# 09_IO_Isolated_Interface.net
KiCad netlist of a schematic drawn in Altium Designer
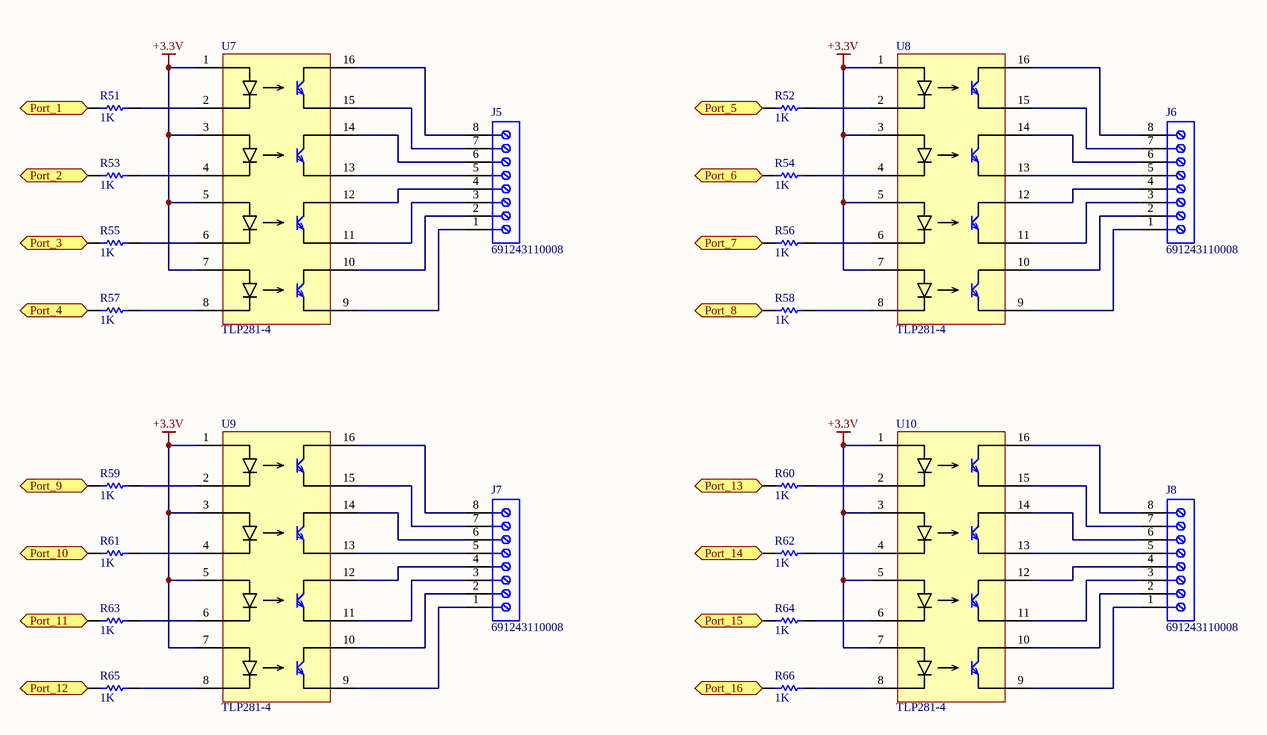
[diagram p0: 09_IO_Isolated_Interface.SchDoc]

(export (version "E")
  (design (tool "Eeschema 10.0.6"))
  (components
    (comp (ref "J5")
      (value "691243110008")
      (footprint "691243110008")
      (description "WR-TBL Serie 2431 Horizontal Cable Entry, Rising Cage Clamp, pitch 3.5mm, 8p")
      (fields (field (name "PUBLISHER") "Wurth Elektronik"))
      (libsource (lib "691322310002.") (part "691243110008"))
    )
    (comp (ref "J6")
      (value "691243110008")
      (footprint "691243110008")
      (description "WR-TBL Serie 2431 Horizontal Cable Entry, Rising Cage Clamp, pitch 3.5mm, 8p")
      (fields (field (name "PUBLISHER") "Wurth Elektronik"))
      (libsource (lib "691322310002.") (part "691243110008"))
    )
    (comp (ref "J7")
      (value "691243110008")
      (footprint "691243110008")
      (description "WR-TBL Serie 2431 Horizontal Cable Entry, Rising Cage Clamp, pitch 3.5mm, 8p")
      (fields (field (name "PUBLISHER") "Wurth Elektronik"))
      (libsource (lib "691322310002.") (part "691243110008"))
    )
    (comp (ref "J8")
      (value "691243110008")
      (footprint "691243110008")
      (description "WR-TBL Serie 2431 Horizontal Cable Entry, Rising Cage Clamp, pitch 3.5mm, 8p")
      (fields (field (name "PUBLISHER") "Wurth Elektronik"))
      (libsource (lib "691322310002.") (part "691243110008"))
    )
    (comp (ref "R51")
      (value "1K")
      (footprint "RES-SM-0603")
      (description "Resistor")
      (fields (field (name "Comment") "RESISTOR SMD"))
      (libsource (lib "PIF_Library") (part "RESISTOR SMD"))
    )
    (comp (ref "R52")
      (value "1K")
      (footprint "RES-SM-0603")
      (description "Resistor")
      (fields (field (name "Comment") "RESISTOR SMD"))
      (libsource (lib "PIF_Library") (part "RESISTOR SMD"))
    )
    (comp (ref "R53")
      (value "1K")
      (footprint "RES-SM-0603")
      (description "Resistor")
      (fields (field (name "Comment") "RESISTOR SMD"))
      (libsource (lib "PIF_Library") (part "RESISTOR SMD"))
    )
    (comp (ref "R54")
      (value "1K")
      (footprint "RES-SM-0603")
      (description "Resistor")
      (fields (field (name "Comment") "RESISTOR SMD"))
      (libsource (lib "PIF_Library") (part "RESISTOR SMD"))
    )
    (comp (ref "R55")
      (value "1K")
      (footprint "RES-SM-0603")
      (description "Resistor")
      (fields (field (name "Comment") "RESISTOR SMD"))
      (libsource (lib "PIF_Library") (part "RESISTOR SMD"))
    )
    (comp (ref "R56")
      (value "1K")
      (footprint "RES-SM-0603")
      (description "Resistor")
      (fields (field (name "Comment") "RESISTOR SMD"))
      (libsource (lib "PIF_Library") (part "RESISTOR SMD"))
    )
    (comp (ref "R57")
      (value "1K")
      (footprint "RES-SM-0603")
      (description "Resistor")
      (fields (field (name "Comment") "RESISTOR SMD"))
      (libsource (lib "PIF_Library") (part "RESISTOR SMD"))
    )
    (comp (ref "R58")
      (value "1K")
      (footprint "RES-SM-0603")
      (description "Resistor")
      (fields (field (name "Comment") "RESISTOR SMD"))
      (libsource (lib "PIF_Library") (part "RESISTOR SMD"))
    )
    (comp (ref "R59")
      (value "1K")
      (footprint "RES-SM-0603")
      (description "Resistor")
      (fields (field (name "Comment") "RESISTOR SMD"))
      (libsource (lib "PIF_Library") (part "RESISTOR SMD"))
    )
    (comp (ref "R60")
      (value "1K")
      (footprint "RES-SM-0603")
      (description "Resistor")
      (fields (field (name "Comment") "RESISTOR SMD"))
      (libsource (lib "PIF_Library") (part "RESISTOR SMD"))
    )
    (comp (ref "R61")
      (value "1K")
      (footprint "RES-SM-0603")
      (description "Resistor")
      (fields (field (name "Comment") "RESISTOR SMD"))
      (libsource (lib "PIF_Library") (part "RESISTOR SMD"))
    )
    (comp (ref "R62")
      (value "1K")
      (footprint "RES-SM-0603")
      (description "Resistor")
      (fields (field (name "Comment") "RESISTOR SMD"))
      (libsource (lib "PIF_Library") (part "RESISTOR SMD"))
    )
    (comp (ref "R63")
      (value "1K")
      (footprint "RES-SM-0603")
      (description "Resistor")
      (fields (field (name "Comment") "RESISTOR SMD"))
      (libsource (lib "PIF_Library") (part "RESISTOR SMD"))
    )
    (comp (ref "R64")
      (value "1K")
      (footprint "RES-SM-0603")
      (description "Resistor")
      (fields (field (name "Comment") "RESISTOR SMD"))
      (libsource (lib "PIF_Library") (part "RESISTOR SMD"))
    )
    (comp (ref "R65")
      (value "1K")
      (footprint "RES-SM-0603")
      (description "Resistor")
      (fields (field (name "Comment") "RESISTOR SMD"))
      (libsource (lib "PIF_Library") (part "RESISTOR SMD"))
    )
    (comp (ref "R66")
      (value "1K")
      (footprint "RES-SM-0603")
      (description "Resistor")
      (fields (field (name "Comment") "RESISTOR SMD"))
      (libsource (lib "PIF_Library") (part "RESISTOR SMD"))
    )
    (comp (ref "U7")
      (value "TLP281-4")
      (footprint "SOIC127P700X210-16N")
      (libsource (lib "MiclsLib") (part "TLP281-4"))
    )
    (comp (ref "U8")
      (value "TLP281-4")
      (footprint "SOIC127P700X210-16N")
      (libsource (lib "MiclsLib") (part "TLP281-4"))
    )
    (comp (ref "U9")
      (value "TLP281-4")
      (footprint "SOIC127P700X210-16N")
      (libsource (lib "MiclsLib") (part "TLP281-4"))
    )
    (comp (ref "U10")
      (value "TLP281-4")
      (footprint "SOIC127P700X210-16N")
      (libsource (lib "MiclsLib") (part "TLP281-4"))
    )
  )
  (nets
    (net (code "1") (name "+3.3V") (class "Default")
      (node (ref "U10") (pin "1") (pinfunction "A1_1") (pintype "passive"))
      (node (ref "U10") (pin "3") (pinfunction "A2_3") (pintype "passive"))
      (node (ref "U10") (pin "5") (pinfunction "A3_5") (pintype "passive"))
      (node (ref "U10") (pin "7") (pinfunction "A4_7") (pintype "passive"))
      (node (ref "U7") (pin "1") (pinfunction "A1_1") (pintype "passive"))
      (node (ref "U7") (pin "3") (pinfunction "A2_3") (pintype "passive"))
      (node (ref "U7") (pin "5") (pinfunction "A3_5") (pintype "passive"))
      (node (ref "U7") (pin "7") (pinfunction "A4_7") (pintype "passive"))
      (node (ref "U8") (pin "1") (pinfunction "A1_1") (pintype "passive"))
      (node (ref "U8") (pin "3") (pinfunction "A2_3") (pintype "passive"))
      (node (ref "U8") (pin "5") (pinfunction "A3_5") (pintype "passive"))
      (node (ref "U8") (pin "7") (pinfunction "A4_7") (pintype "passive"))
      (node (ref "U9") (pin "1") (pinfunction "A1_1") (pintype "passive"))
      (node (ref "U9") (pin "3") (pinfunction "A2_3") (pintype "passive"))
      (node (ref "U9") (pin "5") (pinfunction "A3_5") (pintype "passive"))
      (node (ref "U9") (pin "7") (pinfunction "A4_7") (pintype "passive"))
    )
    (net (code "2") (name "/Port_1") (class "Default")
      (node (ref "R51") (pin "1") (pinfunction "1_1") (pintype "passive"))
    )
    (net (code "3") (name "/Port_2") (class "Default")
      (node (ref "R53") (pin "1") (pinfunction "1_1") (pintype "passive"))
    )
    (net (code "4") (name "/Port_3") (class "Default")
      (node (ref "R55") (pin "1") (pinfunction "1_1") (pintype "passive"))
    )
    (net (code "5") (name "/Port_4") (class "Default")
      (node (ref "R57") (pin "1") (pinfunction "1_1") (pintype "passive"))
    )
    (net (code "6") (name "/Port_5") (class "Default")
      (node (ref "R52") (pin "1") (pinfunction "1_1") (pintype "passive"))
    )
    (net (code "7") (name "/Port_6") (class "Default")
      (node (ref "R54") (pin "1") (pinfunction "1_1") (pintype "passive"))
    )
    (net (code "8") (name "/Port_7") (class "Default")
      (node (ref "R56") (pin "1") (pinfunction "1_1") (pintype "passive"))
    )
    (net (code "9") (name "/Port_8") (class "Default")
      (node (ref "R58") (pin "1") (pinfunction "1_1") (pintype "passive"))
    )
    (net (code "10") (name "/Port_9") (class "Default")
      (node (ref "R59") (pin "1") (pinfunction "1_1") (pintype "passive"))
    )
    (net (code "11") (name "/Port_10") (class "Default")
      (node (ref "R61") (pin "1") (pinfunction "1_1") (pintype "passive"))
    )
    (net (code "12") (name "/Port_11") (class "Default")
      (node (ref "R63") (pin "1") (pinfunction "1_1") (pintype "passive"))
    )
    (net (code "13") (name "/Port_12") (class "Default")
      (node (ref "R65") (pin "1") (pinfunction "1_1") (pintype "passive"))
    )
    (net (code "14") (name "/Port_13") (class "Default")
      (node (ref "R60") (pin "1") (pinfunction "1_1") (pintype "passive"))
    )
    (net (code "15") (name "/Port_14") (class "Default")
      (node (ref "R62") (pin "1") (pinfunction "1_1") (pintype "passive"))
    )
    (net (code "16") (name "/Port_15") (class "Default")
      (node (ref "R64") (pin "1") (pinfunction "1_1") (pintype "passive"))
    )
    (net (code "17") (name "/Port_16") (class "Default")
      (node (ref "R66") (pin "1") (pinfunction "1_1") (pintype "passive"))
    )
    (net (code "18") (name "Net-(U7-C1)") (class "Default")
      (node (ref "R51") (pin "2") (pinfunction "2_2") (pintype "passive"))
      (node (ref "U7") (pin "2") (pinfunction "C1_2") (pintype "passive"))
    )
    (net (code "19") (name "Net-(U7-C2)") (class "Default")
      (node (ref "R53") (pin "2") (pinfunction "2_2") (pintype "passive"))
      (node (ref "U7") (pin "4") (pinfunction "C2_4") (pintype "passive"))
    )
    (net (code "20") (name "Net-(U7-C3)") (class "Default")
      (node (ref "R55") (pin "2") (pinfunction "2_2") (pintype "passive"))
      (node (ref "U7") (pin "6") (pinfunction "C3_6") (pintype "passive"))
    )
    (net (code "21") (name "Net-(U7-C4)") (class "Default")
      (node (ref "R57") (pin "2") (pinfunction "2_2") (pintype "passive"))
      (node (ref "U7") (pin "8") (pinfunction "C4_8") (pintype "passive"))
    )
    (net (code "22") (name "Net-(U7-COL1)") (class "Default")
      (node (ref "J5") (pin "8") (pinfunction "8_8") (pintype "passive"))
      (node (ref "U7") (pin "16") (pinfunction "COL1_16") (pintype "passive"))
    )
    (net (code "23") (name "Net-(U7-COL2)") (class "Default")
      (node (ref "J5") (pin "6") (pinfunction "6_6") (pintype "passive"))
      (node (ref "U7") (pin "14") (pinfunction "COL2_14") (pintype "passive"))
    )
    (net (code "24") (name "Net-(U7-COL3)") (class "Default")
      (node (ref "J5") (pin "4") (pinfunction "4_4") (pintype "passive"))
      (node (ref "U7") (pin "12") (pinfunction "COL3_12") (pintype "passive"))
    )
    (net (code "25") (name "Net-(U7-COL4)") (class "Default")
      (node (ref "J5") (pin "2") (pinfunction "2_2") (pintype "passive"))
      (node (ref "U7") (pin "10") (pinfunction "COL4_10") (pintype "passive"))
    )
    (net (code "26") (name "Net-(U7-E1)") (class "Default")
      (node (ref "J5") (pin "7") (pinfunction "7_7") (pintype "passive"))
      (node (ref "U7") (pin "15") (pinfunction "E1_15") (pintype "passive"))
    )
    (net (code "27") (name "Net-(U7-E2)") (class "Default")
      (node (ref "J5") (pin "5") (pinfunction "5_5") (pintype "passive"))
      (node (ref "U7") (pin "13") (pinfunction "E2_13") (pintype "passive"))
    )
    (net (code "28") (name "Net-(U7-E3)") (class "Default")
      (node (ref "J5") (pin "3") (pinfunction "3_3") (pintype "passive"))
      (node (ref "U7") (pin "11") (pinfunction "E3_11") (pintype "passive"))
    )
    (net (code "29") (name "Net-(U7-E4)") (class "Default")
      (node (ref "J5") (pin "1") (pinfunction "1_1") (pintype "passive"))
      (node (ref "U7") (pin "9") (pinfunction "E4_9") (pintype "passive"))
    )
    (net (code "30") (name "Net-(U8-C1)") (class "Default")
      (node (ref "R52") (pin "2") (pinfunction "2_2") (pintype "passive"))
      (node (ref "U8") (pin "2") (pinfunction "C1_2") (pintype "passive"))
    )
    (net (code "31") (name "Net-(U8-C2)") (class "Default")
      (node (ref "R54") (pin "2") (pinfunction "2_2") (pintype "passive"))
      (node (ref "U8") (pin "4") (pinfunction "C2_4") (pintype "passive"))
    )
    (net (code "32") (name "Net-(U8-C3)") (class "Default")
      (node (ref "R56") (pin "2") (pinfunction "2_2") (pintype "passive"))
      (node (ref "U8") (pin "6") (pinfunction "C3_6") (pintype "passive"))
    )
    (net (code "33") (name "Net-(U8-C4)") (class "Default")
      (node (ref "R58") (pin "2") (pinfunction "2_2") (pintype "passive"))
      (node (ref "U8") (pin "8") (pinfunction "C4_8") (pintype "passive"))
    )
    (net (code "34") (name "Net-(U8-COL1)") (class "Default")
      (node (ref "J6") (pin "8") (pinfunction "8_8") (pintype "passive"))
      (node (ref "U8") (pin "16") (pinfunction "COL1_16") (pintype "passive"))
    )
    (net (code "35") (name "Net-(U8-COL2)") (class "Default")
      (node (ref "J6") (pin "6") (pinfunction "6_6") (pintype "passive"))
      (node (ref "U8") (pin "14") (pinfunction "COL2_14") (pintype "passive"))
    )
    (net (code "36") (name "Net-(U8-COL3)") (class "Default")
      (node (ref "J6") (pin "4") (pinfunction "4_4") (pintype "passive"))
      (node (ref "U8") (pin "12") (pinfunction "COL3_12") (pintype "passive"))
    )
    (net (code "37") (name "Net-(U8-COL4)") (class "Default")
      (node (ref "J6") (pin "2") (pinfunction "2_2") (pintype "passive"))
      (node (ref "U8") (pin "10") (pinfunction "COL4_10") (pintype "passive"))
    )
    (net (code "38") (name "Net-(U8-E1)") (class "Default")
      (node (ref "J6") (pin "7") (pinfunction "7_7") (pintype "passive"))
      (node (ref "U8") (pin "15") (pinfunction "E1_15") (pintype "passive"))
    )
    (net (code "39") (name "Net-(U8-E2)") (class "Default")
      (node (ref "J6") (pin "5") (pinfunction "5_5") (pintype "passive"))
      (node (ref "U8") (pin "13") (pinfunction "E2_13") (pintype "passive"))
    )
    (net (code "40") (name "Net-(U8-E3)") (class "Default")
      (node (ref "J6") (pin "3") (pinfunction "3_3") (pintype "passive"))
      (node (ref "U8") (pin "11") (pinfunction "E3_11") (pintype "passive"))
    )
    (net (code "41") (name "Net-(U8-E4)") (class "Default")
      (node (ref "J6") (pin "1") (pinfunction "1_1") (pintype "passive"))
      (node (ref "U8") (pin "9") (pinfunction "E4_9") (pintype "passive"))
    )
    (net (code "42") (name "Net-(U9-C1)") (class "Default")
      (node (ref "R59") (pin "2") (pinfunction "2_2") (pintype "passive"))
      (node (ref "U9") (pin "2") (pinfunction "C1_2") (pintype "passive"))
    )
    (net (code "43") (name "Net-(U9-C2)") (class "Default")
      (node (ref "R61") (pin "2") (pinfunction "2_2") (pintype "passive"))
      (node (ref "U9") (pin "4") (pinfunction "C2_4") (pintype "passive"))
    )
    (net (code "44") (name "Net-(U9-C3)") (class "Default")
      (node (ref "R63") (pin "2") (pinfunction "2_2") (pintype "passive"))
      (node (ref "U9") (pin "6") (pinfunction "C3_6") (pintype "passive"))
    )
    (net (code "45") (name "Net-(U9-C4)") (class "Default")
      (node (ref "R65") (pin "2") (pinfunction "2_2") (pintype "passive"))
      (node (ref "U9") (pin "8") (pinfunction "C4_8") (pintype "passive"))
    )
    (net (code "46") (name "Net-(U9-COL1)") (class "Default")
      (node (ref "J7") (pin "8") (pinfunction "8_8") (pintype "passive"))
      (node (ref "U9") (pin "16") (pinfunction "COL1_16") (pintype "passive"))
    )
    (net (code "47") (name "Net-(U9-COL2)") (class "Default")
      (node (ref "J7") (pin "6") (pinfunction "6_6") (pintype "passive"))
      (node (ref "U9") (pin "14") (pinfunction "COL2_14") (pintype "passive"))
    )
    (net (code "48") (name "Net-(U9-COL3)") (class "Default")
      (node (ref "J7") (pin "4") (pinfunction "4_4") (pintype "passive"))
      (node (ref "U9") (pin "12") (pinfunction "COL3_12") (pintype "passive"))
    )
    (net (code "49") (name "Net-(U9-COL4)") (class "Default")
      (node (ref "J7") (pin "2") (pinfunction "2_2") (pintype "passive"))
      (node (ref "U9") (pin "10") (pinfunction "COL4_10") (pintype "passive"))
    )
    (net (code "50") (name "Net-(U9-E1)") (class "Default")
      (node (ref "J7") (pin "7") (pinfunction "7_7") (pintype "passive"))
      (node (ref "U9") (pin "15") (pinfunction "E1_15") (pintype "passive"))
    )
    (net (code "51") (name "Net-(U9-E2)") (class "Default")
      (node (ref "J7") (pin "5") (pinfunction "5_5") (pintype "passive"))
      (node (ref "U9") (pin "13") (pinfunction "E2_13") (pintype "passive"))
    )
    (net (code "52") (name "Net-(U9-E3)") (class "Default")
      (node (ref "J7") (pin "3") (pinfunction "3_3") (pintype "passive"))
      (node (ref "U9") (pin "11") (pinfunction "E3_11") (pintype "passive"))
    )
    (net (code "53") (name "Net-(U9-E4)") (class "Default")
      (node (ref "J7") (pin "1") (pinfunction "1_1") (pintype "passive"))
      (node (ref "U9") (pin "9") (pinfunction "E4_9") (pintype "passive"))
    )
    (net (code "54") (name "Net-(U10-C1)") (class "Default")
      (node (ref "R60") (pin "2") (pinfunction "2_2") (pintype "passive"))
      (node (ref "U10") (pin "2") (pinfunction "C1_2") (pintype "passive"))
    )
    (net (code "55") (name "Net-(U10-C2)") (class "Default")
      (node (ref "R62") (pin "2") (pinfunction "2_2") (pintype "passive"))
      (node (ref "U10") (pin "4") (pinfunction "C2_4") (pintype "passive"))
    )
    (net (code "56") (name "Net-(U10-C3)") (class "Default")
      (node (ref "R64") (pin "2") (pinfunction "2_2") (pintype "passive"))
      (node (ref "U10") (pin "6") (pinfunction "C3_6") (pintype "passive"))
    )
    (net (code "57") (name "Net-(U10-C4)") (class "Default")
      (node (ref "R66") (pin "2") (pinfunction "2_2") (pintype "passive"))
      (node (ref "U10") (pin "8") (pinfunction "C4_8") (pintype "passive"))
    )
    (net (code "58") (name "Net-(U10-COL1)") (class "Default")
      (node (ref "J8") (pin "8") (pinfunction "8_8") (pintype "passive"))
      (node (ref "U10") (pin "16") (pinfunction "COL1_16") (pintype "passive"))
    )
    (net (code "59") (name "Net-(U10-COL2)") (class "Default")
      (node (ref "J8") (pin "6") (pinfunction "6_6") (pintype "passive"))
      (node (ref "U10") (pin "14") (pinfunction "COL2_14") (pintype "passive"))
    )
    (net (code "60") (name "Net-(U10-COL3)") (class "Default")
      (node (ref "J8") (pin "4") (pinfunction "4_4") (pintype "passive"))
      (node (ref "U10") (pin "12") (pinfunction "COL3_12") (pintype "passive"))
    )
    (net (code "61") (name "Net-(U10-COL4)") (class "Default")
      (node (ref "J8") (pin "2") (pinfunction "2_2") (pintype "passive"))
      (node (ref "U10") (pin "10") (pinfunction "COL4_10") (pintype "passive"))
    )
    (net (code "62") (name "Net-(U10-E1)") (class "Default")
      (node (ref "J8") (pin "7") (pinfunction "7_7") (pintype "passive"))
      (node (ref "U10") (pin "15") (pinfunction "E1_15") (pintype "passive"))
    )
    (net (code "63") (name "Net-(U10-E2)") (class "Default")
      (node (ref "J8") (pin "5") (pinfunction "5_5") (pintype "passive"))
      (node (ref "U10") (pin "13") (pinfunction "E2_13") (pintype "passive"))
    )
    (net (code "64") (name "Net-(U10-E3)") (class "Default")
      (node (ref "J8") (pin "3") (pinfunction "3_3") (pintype "passive"))
      (node (ref "U10") (pin "11") (pinfunction "E3_11") (pintype "passive"))
    )
    (net (code "65") (name "Net-(U10-E4)") (class "Default")
      (node (ref "J8") (pin "1") (pinfunction "1_1") (pintype "passive"))
      (node (ref "U10") (pin "9") (pinfunction "E4_9") (pintype "passive"))
    )
  )
)
